# Connectors.net
KiCad netlist of a schematic drawn in Altium Designer
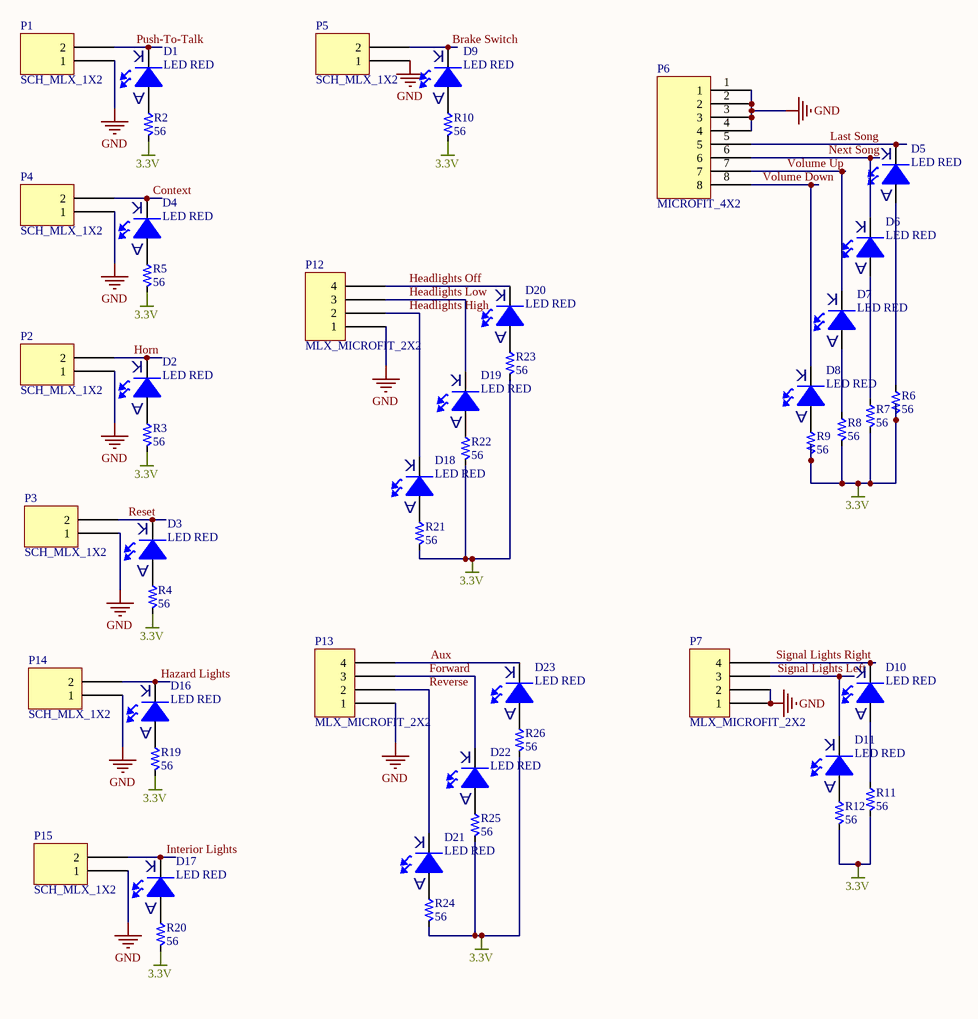
[diagram p0: Connectors.SchDoc]

(export (version "E")
  (design (tool "Eeschema 10.0.6"))
  (components
    (comp (ref "D1")
      (value "LED RED")
      (footprint "RED LED")
      (libsource (lib "LED RED 150141RS73100") (part "LED RED"))
    )
    (comp (ref "D2")
      (value "LED RED")
      (footprint "RED LED")
      (libsource (lib "LED RED 150141RS73100") (part "LED RED"))
    )
    (comp (ref "D3")
      (value "LED RED")
      (footprint "RED LED")
      (libsource (lib "LED RED 150141RS73100") (part "LED RED"))
    )
    (comp (ref "D4")
      (value "LED RED")
      (footprint "RED LED")
      (libsource (lib "LED RED 150141RS73100") (part "LED RED"))
    )
    (comp (ref "D5")
      (value "LED RED")
      (footprint "RED LED")
      (libsource (lib "LED RED 150141RS73100") (part "LED RED"))
    )
    (comp (ref "D6")
      (value "LED RED")
      (footprint "RED LED")
      (libsource (lib "LED RED 150141RS73100") (part "LED RED"))
    )
    (comp (ref "D7")
      (value "LED RED")
      (footprint "RED LED")
      (libsource (lib "LED RED 150141RS73100") (part "LED RED"))
    )
    (comp (ref "D8")
      (value "LED RED")
      (footprint "RED LED")
      (libsource (lib "LED RED 150141RS73100") (part "LED RED"))
    )
    (comp (ref "D9")
      (value "LED RED")
      (footprint "RED LED")
      (libsource (lib "LED RED 150141RS73100") (part "LED RED"))
    )
    (comp (ref "D10")
      (value "LED RED")
      (footprint "RED LED")
      (libsource (lib "LED RED 150141RS73100") (part "LED RED"))
    )
    (comp (ref "D11")
      (value "LED RED")
      (footprint "RED LED")
      (libsource (lib "LED RED 150141RS73100") (part "LED RED"))
    )
    (comp (ref "D16")
      (value "LED RED")
      (footprint "RED LED")
      (libsource (lib "LED RED 150141RS73100") (part "LED RED"))
    )
    (comp (ref "D17")
      (value "LED RED")
      (footprint "RED LED")
      (libsource (lib "LED RED 150141RS73100") (part "LED RED"))
    )
    (comp (ref "D18")
      (value "LED RED")
      (footprint "RED LED")
      (libsource (lib "LED RED 150141RS73100") (part "LED RED"))
    )
    (comp (ref "D19")
      (value "LED RED")
      (footprint "RED LED")
      (libsource (lib "LED RED 150141RS73100") (part "LED RED"))
    )
    (comp (ref "D20")
      (value "LED RED")
      (footprint "RED LED")
      (libsource (lib "LED RED 150141RS73100") (part "LED RED"))
    )
    (comp (ref "D21")
      (value "LED RED")
      (footprint "RED LED")
      (libsource (lib "LED RED 150141RS73100") (part "LED RED"))
    )
    (comp (ref "D22")
      (value "LED RED")
      (footprint "RED LED")
      (libsource (lib "LED RED 150141RS73100") (part "LED RED"))
    )
    (comp (ref "D23")
      (value "LED RED")
      (footprint "RED LED")
      (libsource (lib "LED RED 150141RS73100") (part "LED RED"))
    )
    (comp (ref "P1")
      (value "SCH_MLX_1X2")
      (footprint "PCB_MLX_MICROFIT_1X2")
      (libsource (lib "MLX_MICROFIT_1X2_SCH") (part "SCH_MLX_1X2"))
    )
    (comp (ref "P2")
      (value "SCH_MLX_1X2")
      (footprint "PCB_MLX_MICROFIT_1X2")
      (libsource (lib "MLX_MICROFIT_1X2_SCH") (part "SCH_MLX_1X2"))
    )
    (comp (ref "P3")
      (value "SCH_MLX_1X2")
      (footprint "PCB_MLX_MICROFIT_1X2")
      (libsource (lib "MLX_MICROFIT_1X2_SCH") (part "SCH_MLX_1X2"))
    )
    (comp (ref "P4")
      (value "SCH_MLX_1X2")
      (footprint "PCB_MLX_MICROFIT_1X2")
      (libsource (lib "MLX_MICROFIT_1X2_SCH") (part "SCH_MLX_1X2"))
    )
    (comp (ref "P5")
      (value "SCH_MLX_1X2")
      (footprint "PCB_MLX_MICROFIT_1X2")
      (libsource (lib "MLX_MICROFIT_1X2_SCH") (part "SCH_MLX_1X2"))
    )
    (comp (ref "P6")
      (value "MICROFIT_4X2")
      (footprint "PCB_MLX_MICROFIT_4X2_P:PCB_MLX_MICROFIT_4X2")
      (description "Molex Microfit Connector 4x2")
      (libsource (lib "SCH_MLX_MICROFIT_4X2_P") (part "SCH_MLX_MICROFIT_4X2"))
    )
    (comp (ref "P7")
      (value "MLX_MICROFIT_2X2")
      (footprint "MLX_MICROFIT_2X2")
      (libsource (lib "MLX_MICROFIT_2X2_SCH") (part "MLX_MICROFIT_2X2"))
    )
    (comp (ref "P12")
      (value "MLX_MICROFIT_2X2")
      (footprint "MLX_MICROFIT_2X2")
      (libsource (lib "MLX_MICROFIT_2X2_SCH") (part "MLX_MICROFIT_2X2"))
    )
    (comp (ref "P13")
      (value "MLX_MICROFIT_2X2")
      (footprint "MLX_MICROFIT_2X2")
      (libsource (lib "MLX_MICROFIT_2X2_SCH") (part "MLX_MICROFIT_2X2"))
    )
    (comp (ref "P14")
      (value "SCH_MLX_1X2")
      (footprint "PCB_MLX_MICROFIT_1X2")
      (libsource (lib "MLX_MICROFIT_1X2_SCH") (part "SCH_MLX_1X2"))
    )
    (comp (ref "P15")
      (value "SCH_MLX_1X2")
      (footprint "PCB_MLX_MICROFIT_1X2")
      (libsource (lib "MLX_MICROFIT_1X2_SCH") (part "SCH_MLX_1X2"))
    )
    (comp (ref "R2")
      (value "SCH_GENERIC_RESISTOR_0603")
      (footprint "PCB_GENERIC_SMD_0603")
      (description "Generic SMD resistor 0603")
      (fields (field (name "RESISTANCE") "56"))
      (libsource (lib "SCH_GENERIC_RESISTOR_0603") (part "SCH_GENERIC_RESISTOR_0603"))
    )
    (comp (ref "R3")
      (value "SCH_GENERIC_RESISTOR_0603")
      (footprint "PCB_GENERIC_SMD_0603")
      (description "Generic SMD resistor 0603")
      (fields (field (name "RESISTANCE") "56"))
      (libsource (lib "SCH_GENERIC_RESISTOR_0603") (part "SCH_GENERIC_RESISTOR_0603"))
    )
    (comp (ref "R4")
      (value "SCH_GENERIC_RESISTOR_0603")
      (footprint "PCB_GENERIC_SMD_0603")
      (description "Generic SMD resistor 0603")
      (fields (field (name "RESISTANCE") "56"))
      (libsource (lib "SCH_GENERIC_RESISTOR_0603") (part "SCH_GENERIC_RESISTOR_0603"))
    )
    (comp (ref "R5")
      (value "SCH_GENERIC_RESISTOR_0603")
      (footprint "PCB_GENERIC_SMD_0603")
      (description "Generic SMD resistor 0603")
      (fields (field (name "RESISTANCE") "56"))
      (libsource (lib "SCH_GENERIC_RESISTOR_0603") (part "SCH_GENERIC_RESISTOR_0603"))
    )
    (comp (ref "R6")
      (value "SCH_GENERIC_RESISTOR_0603")
      (footprint "PCB_GENERIC_SMD_0603")
      (description "Generic SMD resistor 0603")
      (fields (field (name "RESISTANCE") "56"))
      (libsource (lib "SCH_GENERIC_RESISTOR_0603") (part "SCH_GENERIC_RESISTOR_0603"))
    )
    (comp (ref "R7")
      (value "SCH_GENERIC_RESISTOR_0603")
      (footprint "PCB_GENERIC_SMD_0603")
      (description "Generic SMD resistor 0603")
      (fields (field (name "RESISTANCE") "56"))
      (libsource (lib "SCH_GENERIC_RESISTOR_0603") (part "SCH_GENERIC_RESISTOR_0603"))
    )
    (comp (ref "R8")
      (value "SCH_GENERIC_RESISTOR_0603")
      (footprint "PCB_GENERIC_SMD_0603")
      (description "Generic SMD resistor 0603")
      (fields (field (name "RESISTANCE") "56"))
      (libsource (lib "SCH_GENERIC_RESISTOR_0603") (part "SCH_GENERIC_RESISTOR_0603"))
    )
    (comp (ref "R9")
      (value "SCH_GENERIC_RESISTOR_0603")
      (footprint "PCB_GENERIC_SMD_0603")
      (description "Generic SMD resistor 0603")
      (fields (field (name "RESISTANCE") "56"))
      (libsource (lib "SCH_GENERIC_RESISTOR_0603") (part "SCH_GENERIC_RESISTOR_0603"))
    )
    (comp (ref "R10")
      (value "SCH_GENERIC_RESISTOR_0603")
      (footprint "PCB_GENERIC_SMD_0603")
      (description "Generic SMD resistor 0603")
      (fields (field (name "RESISTANCE") "56"))
      (libsource (lib "SCH_GENERIC_RESISTOR_0603") (part "SCH_GENERIC_RESISTOR_0603"))
    )
    (comp (ref "R11")
      (value "SCH_GENERIC_RESISTOR_0603")
      (footprint "PCB_GENERIC_SMD_0603")
      (description "Generic SMD resistor 0603")
      (fields (field (name "RESISTANCE") "56"))
      (libsource (lib "SCH_GENERIC_RESISTOR_0603") (part "SCH_GENERIC_RESISTOR_0603"))
    )
    (comp (ref "R12")
      (value "SCH_GENERIC_RESISTOR_0603")
      (footprint "PCB_GENERIC_SMD_0603")
      (description "Generic SMD resistor 0603")
      (fields (field (name "RESISTANCE") "56"))
      (libsource (lib "SCH_GENERIC_RESISTOR_0603") (part "SCH_GENERIC_RESISTOR_0603"))
    )
    (comp (ref "R19")
      (value "SCH_GENERIC_RESISTOR_0603")
      (footprint "PCB_GENERIC_SMD_0603")
      (description "Generic SMD resistor 0603")
      (fields (field (name "RESISTANCE") "56"))
      (libsource (lib "SCH_GENERIC_RESISTOR_0603") (part "SCH_GENERIC_RESISTOR_0603"))
    )
    (comp (ref "R20")
      (value "SCH_GENERIC_RESISTOR_0603")
      (footprint "PCB_GENERIC_SMD_0603")
      (description "Generic SMD resistor 0603")
      (fields (field (name "RESISTANCE") "56"))
      (libsource (lib "SCH_GENERIC_RESISTOR_0603") (part "SCH_GENERIC_RESISTOR_0603"))
    )
    (comp (ref "R21")
      (value "SCH_GENERIC_RESISTOR_0603")
      (footprint "PCB_GENERIC_SMD_0603")
      (description "Generic SMD resistor 0603")
      (fields (field (name "RESISTANCE") "56"))
      (libsource (lib "SCH_GENERIC_RESISTOR_0603") (part "SCH_GENERIC_RESISTOR_0603"))
    )
    (comp (ref "R22")
      (value "SCH_GENERIC_RESISTOR_0603")
      (footprint "PCB_GENERIC_SMD_0603")
      (description "Generic SMD resistor 0603")
      (fields (field (name "RESISTANCE") "56"))
      (libsource (lib "SCH_GENERIC_RESISTOR_0603") (part "SCH_GENERIC_RESISTOR_0603"))
    )
    (comp (ref "R23")
      (value "SCH_GENERIC_RESISTOR_0603")
      (footprint "PCB_GENERIC_SMD_0603")
      (description "Generic SMD resistor 0603")
      (fields (field (name "RESISTANCE") "56"))
      (libsource (lib "SCH_GENERIC_RESISTOR_0603") (part "SCH_GENERIC_RESISTOR_0603"))
    )
    (comp (ref "R24")
      (value "SCH_GENERIC_RESISTOR_0603")
      (footprint "PCB_GENERIC_SMD_0603")
      (description "Generic SMD resistor 0603")
      (fields (field (name "RESISTANCE") "56"))
      (libsource (lib "SCH_GENERIC_RESISTOR_0603") (part "SCH_GENERIC_RESISTOR_0603"))
    )
    (comp (ref "R25")
      (value "SCH_GENERIC_RESISTOR_0603")
      (footprint "PCB_GENERIC_SMD_0603")
      (description "Generic SMD resistor 0603")
      (fields (field (name "RESISTANCE") "56"))
      (libsource (lib "SCH_GENERIC_RESISTOR_0603") (part "SCH_GENERIC_RESISTOR_0603"))
    )
    (comp (ref "R26")
      (value "SCH_GENERIC_RESISTOR_0603")
      (footprint "PCB_GENERIC_SMD_0603")
      (description "Generic SMD resistor 0603")
      (fields (field (name "RESISTANCE") "56"))
      (libsource (lib "SCH_GENERIC_RESISTOR_0603") (part "SCH_GENERIC_RESISTOR_0603"))
    )
  )
  (nets
    (net (code "1") (name "/Aux") (class "Default")
      (node (ref "D23") (pin "1") (pintype "passive"))
      (node (ref "P13") (pin "4") (pinfunction "4_4") (pintype "passive"))
    )
    (net (code "2") (name "/Brake Switch") (class "Default")
      (node (ref "D9") (pin "1") (pintype "passive"))
      (node (ref "P5") (pin "2") (pinfunction "2_2") (pintype "passive"))
    )
    (net (code "3") (name "/Context") (class "Default")
      (node (ref "D4") (pin "1") (pintype "passive"))
      (node (ref "P4") (pin "2") (pinfunction "2_2") (pintype "passive"))
    )
    (net (code "4") (name "/Forward") (class "Default")
      (node (ref "D22") (pin "1") (pintype "passive"))
      (node (ref "P13") (pin "3") (pinfunction "3_3") (pintype "passive"))
    )
    (net (code "5") (name "/Hazard Lights") (class "Default")
      (node (ref "D16") (pin "1") (pintype "passive"))
      (node (ref "P14") (pin "2") (pinfunction "2_2") (pintype "passive"))
    )
    (net (code "6") (name "/Headlights High") (class "Default")
      (node (ref "D18") (pin "1") (pintype "passive"))
      (node (ref "P12") (pin "2") (pinfunction "2_2") (pintype "passive"))
    )
    (net (code "7") (name "/Headlights Low") (class "Default")
      (node (ref "D19") (pin "1") (pintype "passive"))
      (node (ref "P12") (pin "3") (pinfunction "3_3") (pintype "passive"))
    )
    (net (code "8") (name "/Headlights Off") (class "Default")
      (node (ref "D20") (pin "1") (pintype "passive"))
      (node (ref "P12") (pin "4") (pinfunction "4_4") (pintype "passive"))
    )
    (net (code "9") (name "/Horn") (class "Default")
      (node (ref "D2") (pin "1") (pintype "passive"))
      (node (ref "P2") (pin "2") (pinfunction "2_2") (pintype "passive"))
    )
    (net (code "10") (name "/Interior Lights") (class "Default")
      (node (ref "D17") (pin "1") (pintype "passive"))
      (node (ref "P15") (pin "2") (pinfunction "2_2") (pintype "passive"))
    )
    (net (code "11") (name "/Last Song") (class "Default")
      (node (ref "D5") (pin "1") (pintype "passive"))
      (node (ref "P6") (pin "5") (pinfunction "5_5") (pintype "passive"))
    )
    (net (code "12") (name "/Next Song") (class "Default")
      (node (ref "D6") (pin "1") (pintype "passive"))
      (node (ref "P6") (pin "6") (pinfunction "6_6") (pintype "passive"))
    )
    (net (code "13") (name "/Push-To-Talk") (class "Default")
      (node (ref "D1") (pin "1") (pintype "passive"))
      (node (ref "P1") (pin "2") (pinfunction "2_2") (pintype "passive"))
    )
    (net (code "14") (name "/Reset") (class "Default")
      (node (ref "D3") (pin "1") (pintype "passive"))
      (node (ref "P3") (pin "2") (pinfunction "2_2") (pintype "passive"))
    )
    (net (code "15") (name "/Reverse") (class "Default")
      (node (ref "D21") (pin "1") (pintype "passive"))
      (node (ref "P13") (pin "2") (pinfunction "2_2") (pintype "passive"))
    )
    (net (code "16") (name "/Signal Lights Left") (class "Default")
      (node (ref "D11") (pin "1") (pintype "passive"))
      (node (ref "P7") (pin "3") (pinfunction "3_3") (pintype "passive"))
    )
    (net (code "17") (name "/Signal Lights Right") (class "Default")
      (node (ref "D10") (pin "1") (pintype "passive"))
      (node (ref "P7") (pin "4") (pinfunction "4_4") (pintype "passive"))
    )
    (net (code "18") (name "/Volume Down") (class "Default")
      (node (ref "D8") (pin "1") (pintype "passive"))
      (node (ref "P6") (pin "8") (pinfunction "8_8") (pintype "passive"))
    )
    (net (code "19") (name "/Volume Up") (class "Default")
      (node (ref "D7") (pin "1") (pintype "passive"))
      (node (ref "P6") (pin "7") (pinfunction "7_7") (pintype "passive"))
    )
    (net (code "20") (name "3.3V") (class "Default")
      (node (ref "R10") (pin "2") (pinfunction "2_2") (pintype "passive"))
      (node (ref "R11") (pin "2") (pinfunction "2_2") (pintype "passive"))
      (node (ref "R12") (pin "2") (pinfunction "2_2") (pintype "passive"))
      (node (ref "R19") (pin "2") (pinfunction "2_2") (pintype "passive"))
      (node (ref "R2") (pin "2") (pinfunction "2_2") (pintype "passive"))
      (node (ref "R20") (pin "2") (pinfunction "2_2") (pintype "passive"))
      (node (ref "R21") (pin "2") (pinfunction "2_2") (pintype "passive"))
      (node (ref "R22") (pin "2") (pinfunction "2_2") (pintype "passive"))
      (node (ref "R23") (pin "2") (pinfunction "2_2") (pintype "passive"))
      (node (ref "R24") (pin "2") (pinfunction "2_2") (pintype "passive"))
      (node (ref "R25") (pin "2") (pinfunction "2_2") (pintype "passive"))
      (node (ref "R26") (pin "2") (pinfunction "2_2") (pintype "passive"))
      (node (ref "R3") (pin "2") (pinfunction "2_2") (pintype "passive"))
      (node (ref "R4") (pin "2") (pinfunction "2_2") (pintype "passive"))
      (node (ref "R5") (pin "2") (pinfunction "2_2") (pintype "passive"))
      (node (ref "R6") (pin "2") (pinfunction "2_2") (pintype "passive"))
      (node (ref "R7") (pin "2") (pinfunction "2_2") (pintype "passive"))
      (node (ref "R8") (pin "2") (pinfunction "2_2") (pintype "passive"))
      (node (ref "R9") (pin "2") (pinfunction "2_2") (pintype "passive"))
    )
    (net (code "21") (name "GND") (class "Default")
      (node (ref "P1") (pin "1") (pinfunction "1_1") (pintype "passive"))
      (node (ref "P12") (pin "1") (pinfunction "1_1") (pintype "passive"))
      (node (ref "P13") (pin "1") (pinfunction "1_1") (pintype "passive"))
      (node (ref "P14") (pin "1") (pinfunction "1_1") (pintype "passive"))
      (node (ref "P15") (pin "1") (pinfunction "1_1") (pintype "passive"))
      (node (ref "P2") (pin "1") (pinfunction "1_1") (pintype "passive"))
      (node (ref "P3") (pin "1") (pinfunction "1_1") (pintype "passive"))
      (node (ref "P4") (pin "1") (pinfunction "1_1") (pintype "passive"))
      (node (ref "P5") (pin "1") (pinfunction "1_1") (pintype "passive"))
      (node (ref "P6") (pin "1") (pinfunction "1_1") (pintype "passive"))
      (node (ref "P6") (pin "2") (pinfunction "2_2") (pintype "passive"))
      (node (ref "P6") (pin "3") (pinfunction "3_3") (pintype "passive"))
      (node (ref "P6") (pin "4") (pinfunction "4_4") (pintype "passive"))
      (node (ref "P7") (pin "1") (pinfunction "1_1") (pintype "passive"))
      (node (ref "P7") (pin "2") (pinfunction "2_2") (pintype "passive"))
    )
    (net (code "22") (name "Net-(D1-Pad2)") (class "Default")
      (node (ref "D1") (pin "2") (pintype "passive"))
      (node (ref "R2") (pin "1") (pinfunction "1_1") (pintype "passive"))
    )
    (net (code "23") (name "Net-(D2-Pad2)") (class "Default")
      (node (ref "D2") (pin "2") (pintype "passive"))
      (node (ref "R3") (pin "1") (pinfunction "1_1") (pintype "passive"))
    )
    (net (code "24") (name "Net-(D3-Pad2)") (class "Default")
      (node (ref "D3") (pin "2") (pintype "passive"))
      (node (ref "R4") (pin "1") (pinfunction "1_1") (pintype "passive"))
    )
    (net (code "25") (name "Net-(D4-Pad2)") (class "Default")
      (node (ref "D4") (pin "2") (pintype "passive"))
      (node (ref "R5") (pin "1") (pinfunction "1_1") (pintype "passive"))
    )
    (net (code "26") (name "Net-(D5-Pad2)") (class "Default")
      (node (ref "D5") (pin "2") (pintype "passive"))
      (node (ref "R6") (pin "1") (pinfunction "1_1") (pintype "passive"))
    )
    (net (code "27") (name "Net-(D6-Pad2)") (class "Default")
      (node (ref "D6") (pin "2") (pintype "passive"))
      (node (ref "R7") (pin "1") (pinfunction "1_1") (pintype "passive"))
    )
    (net (code "28") (name "Net-(D7-Pad2)") (class "Default")
      (node (ref "D7") (pin "2") (pintype "passive"))
      (node (ref "R8") (pin "1") (pinfunction "1_1") (pintype "passive"))
    )
    (net (code "29") (name "Net-(D8-Pad2)") (class "Default")
      (node (ref "D8") (pin "2") (pintype "passive"))
      (node (ref "R9") (pin "1") (pinfunction "1_1") (pintype "passive"))
    )
    (net (code "30") (name "Net-(D9-Pad2)") (class "Default")
      (node (ref "D9") (pin "2") (pintype "passive"))
      (node (ref "R10") (pin "1") (pinfunction "1_1") (pintype "passive"))
    )
    (net (code "31") (name "Net-(D10-Pad2)") (class "Default")
      (node (ref "D10") (pin "2") (pintype "passive"))
      (node (ref "R11") (pin "1") (pinfunction "1_1") (pintype "passive"))
    )
    (net (code "32") (name "Net-(D11-Pad2)") (class "Default")
      (node (ref "D11") (pin "2") (pintype "passive"))
      (node (ref "R12") (pin "1") (pinfunction "1_1") (pintype "passive"))
    )
    (net (code "33") (name "Net-(D16-Pad2)") (class "Default")
      (node (ref "D16") (pin "2") (pintype "passive"))
      (node (ref "R19") (pin "1") (pinfunction "1_1") (pintype "passive"))
    )
    (net (code "34") (name "Net-(D17-Pad2)") (class "Default")
      (node (ref "D17") (pin "2") (pintype "passive"))
      (node (ref "R20") (pin "1") (pinfunction "1_1") (pintype "passive"))
    )
    (net (code "35") (name "Net-(D18-Pad2)") (class "Default")
      (node (ref "D18") (pin "2") (pintype "passive"))
      (node (ref "R21") (pin "1") (pinfunction "1_1") (pintype "passive"))
    )
    (net (code "36") (name "Net-(D19-Pad2)") (class "Default")
      (node (ref "D19") (pin "2") (pintype "passive"))
      (node (ref "R22") (pin "1") (pinfunction "1_1") (pintype "passive"))
    )
    (net (code "37") (name "Net-(D20-Pad2)") (class "Default")
      (node (ref "D20") (pin "2") (pintype "passive"))
      (node (ref "R23") (pin "1") (pinfunction "1_1") (pintype "passive"))
    )
    (net (code "38") (name "Net-(D21-Pad2)") (class "Default")
      (node (ref "D21") (pin "2") (pintype "passive"))
      (node (ref "R24") (pin "1") (pinfunction "1_1") (pintype "passive"))
    )
    (net (code "39") (name "Net-(D22-Pad2)") (class "Default")
      (node (ref "D22") (pin "2") (pintype "passive"))
      (node (ref "R25") (pin "1") (pinfunction "1_1") (pintype "passive"))
    )
    (net (code "40") (name "Net-(D23-Pad2)") (class "Default")
      (node (ref "D23") (pin "2") (pintype "passive"))
      (node (ref "R26") (pin "1") (pinfunction "1_1") (pintype "passive"))
    )
  )
)
